# RiskChemi_Sensors_V2_05M1.net
KiCad netlist of a schematic drawn in Altium Designer
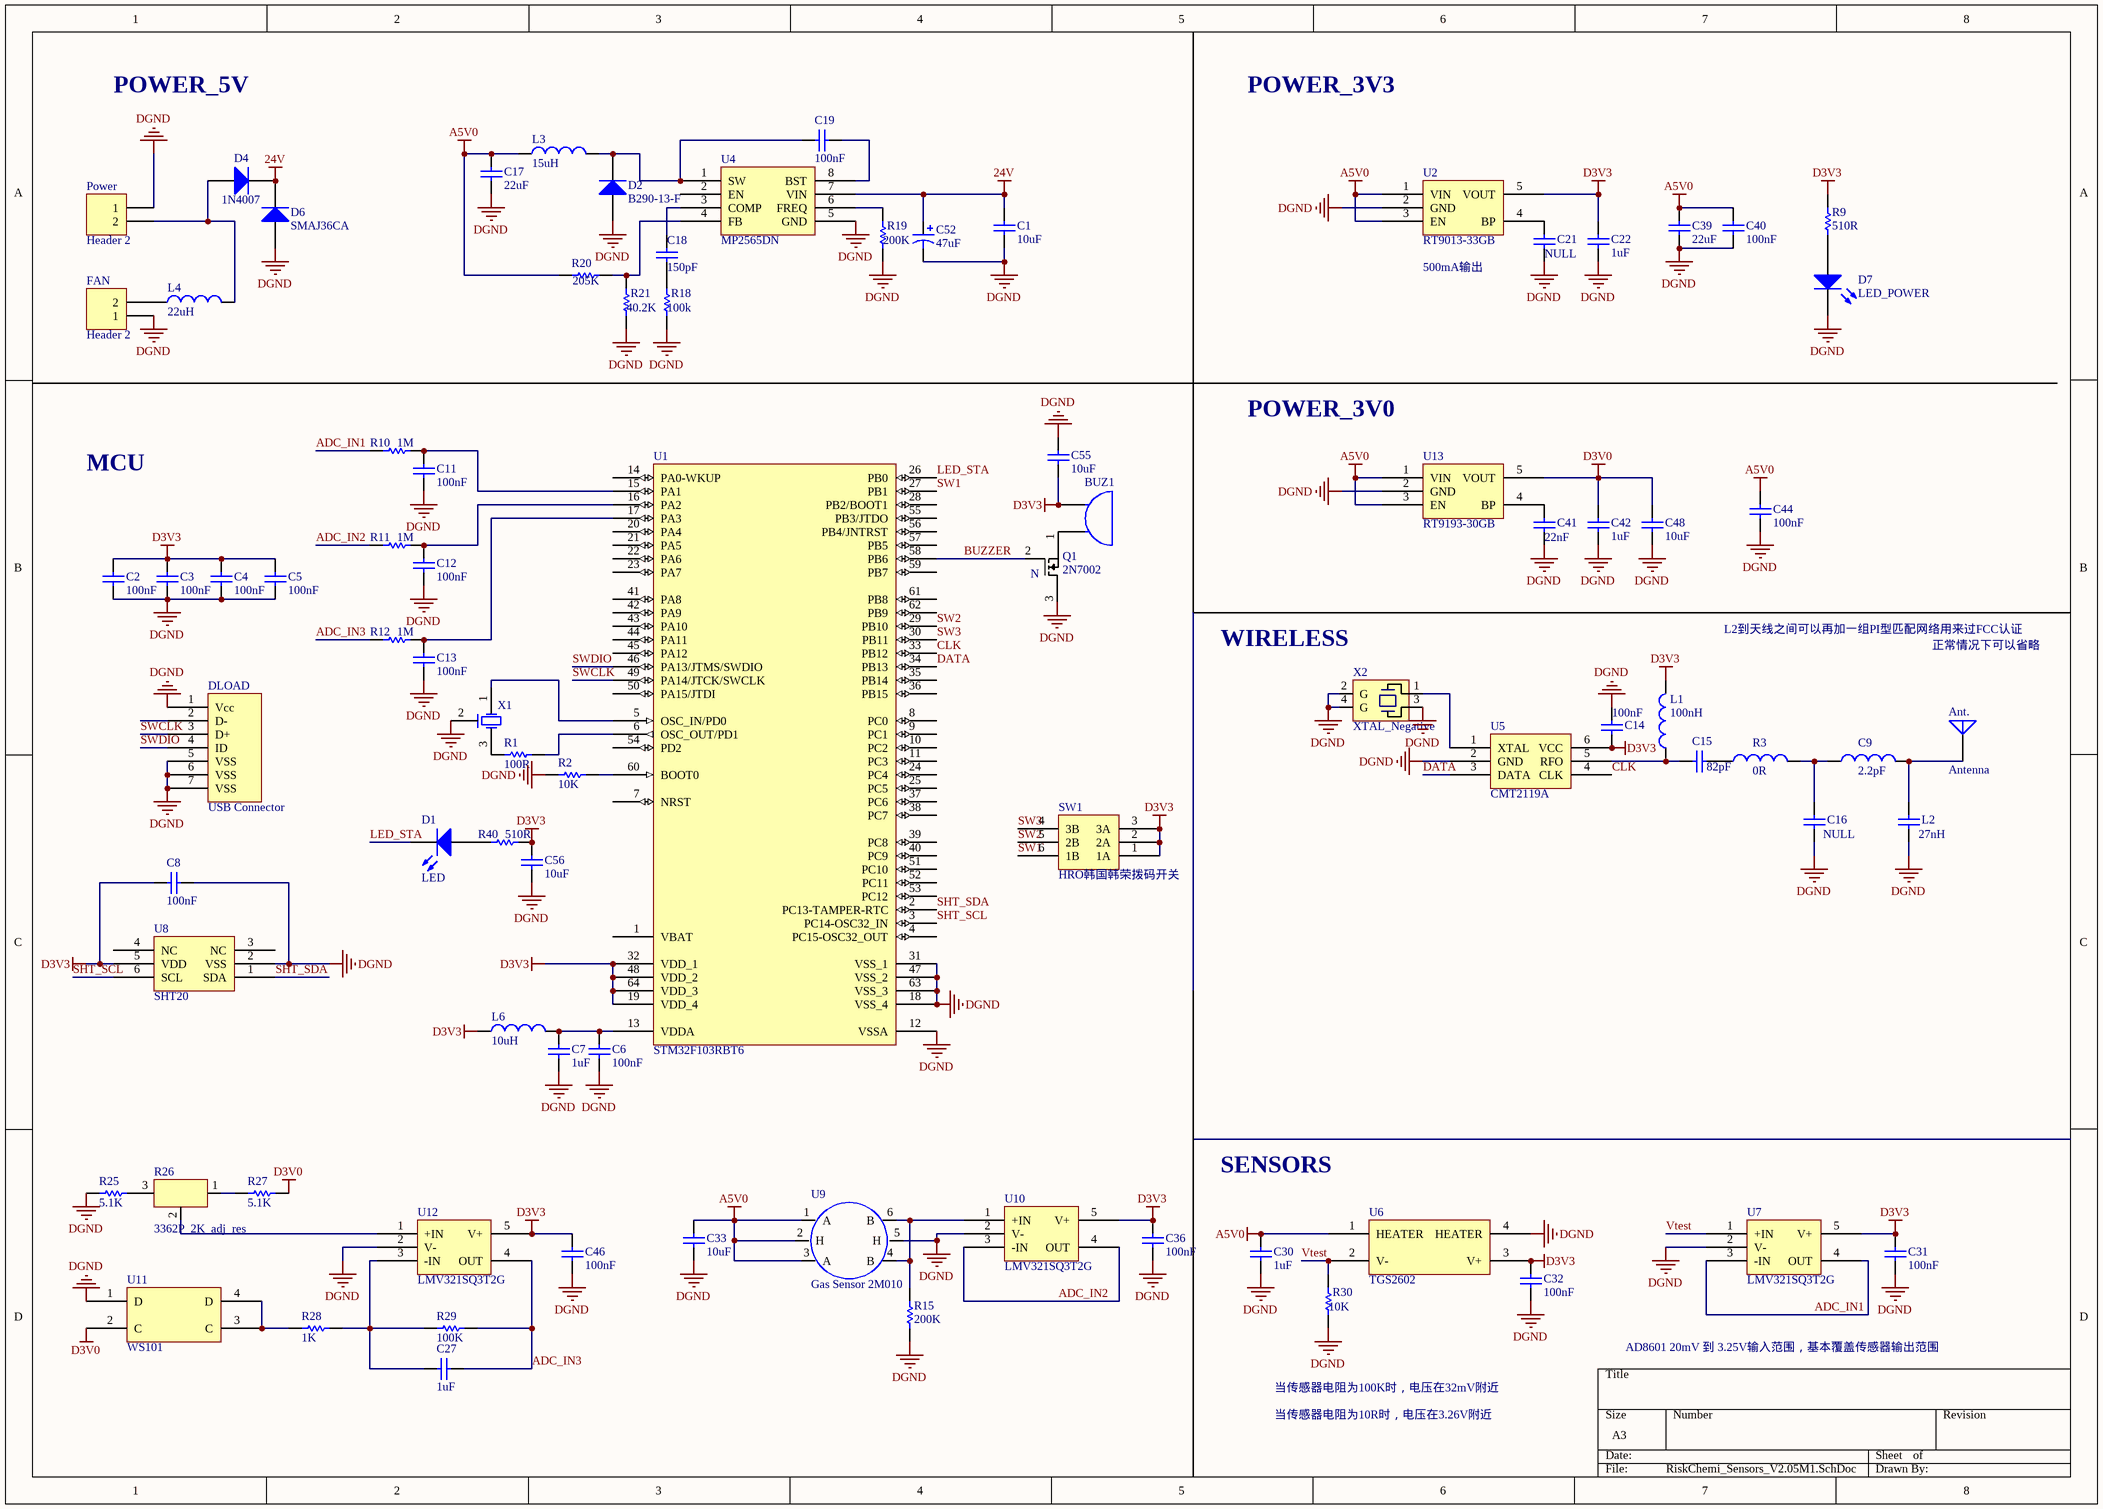
[diagram p0: RiskChemi_Sensors_V2.05M1.SchDoc]

(export (version "E")
  (design (tool "Eeschema 10.0.6"))
  (components
    (comp (ref "Ant.")
      (value "Antenna")
      (footprint "PIN1")
      (description "Generic Antenna")
      (fields (field (name "PUBLISHER") "Altium Limited"))
      (libsource (lib "Miscellaneous Devices") (part "Antenna"))
    )
    (comp (ref "BUZ1")
      (value "BUZZER 0905 through hole")
      (footprint "BUZ0905")
      (description "Buzzer")
      (libsource (lib "杂元件库") (part "BUZZER"))
    )
    (comp (ref "C1")
      (value "10uF")
      (footprint "0805")
      (description "Capacitor,50V")
      (fields (field (name "PUBLISHER") "Altium Limited"))
      (libsource (lib "Miscellaneous Devices") (part "Cap"))
    )
    (comp (ref "C2")
      (value "100nF")
      (footprint "BinFeng:0603")
      (description "Capacitor")
      (fields (field (name "PUBLISHER") "Altium Limited"))
      (libsource (lib "Miscellaneous Devices") (part "Cap"))
    )
    (comp (ref "C3")
      (value "100nF")
      (footprint "BinFeng:0603")
      (description "Capacitor")
      (fields (field (name "PUBLISHER") "Altium Limited"))
      (libsource (lib "Miscellaneous Devices") (part "Cap"))
    )
    (comp (ref "C4")
      (value "100nF")
      (footprint "BinFeng:0603")
      (description "Capacitor")
      (fields (field (name "PUBLISHER") "Altium Limited"))
      (libsource (lib "Miscellaneous Devices") (part "Cap"))
    )
    (comp (ref "C5")
      (value "100nF")
      (footprint "BinFeng:0603")
      (description "Capacitor")
      (fields (field (name "PUBLISHER") "Altium Limited"))
      (libsource (lib "Miscellaneous Devices") (part "Cap"))
    )
    (comp (ref "C6")
      (value "100nF")
      (footprint "BinFeng:0603")
      (description "Capacitor")
      (fields (field (name "PUBLISHER") "Altium Limited"))
      (libsource (lib "Miscellaneous Devices") (part "Cap"))
    )
    (comp (ref "C7")
      (value "1uF")
      (footprint "BinFeng:0603")
      (description "Capacitor")
      (fields (field (name "PUBLISHER") "Altium Limited"))
      (libsource (lib "Miscellaneous Devices") (part "Cap"))
    )
    (comp (ref "C8")
      (value "100nF")
      (footprint "BinFeng:0603")
      (description "Capacitor")
      (fields (field (name "PUBLISHER") "Altium Limited"))
      (libsource (lib "Miscellaneous Devices") (part "Cap"))
    )
    (comp (ref "C9")
      (value "2.2pF")
      (footprint "0603C")
      (description "Inductor")
      (fields (field (name "PUBLISHER") "Altium Limited"))
      (libsource (lib "Miscellaneous Devices") (part "Inductor"))
    )
    (comp (ref "C11")
      (value "100nF")
      (footprint "BinFeng:0603")
      (description "Capacitor")
      (fields (field (name "PUBLISHER") "Altium Limited"))
      (libsource (lib "Miscellaneous Devices") (part "Cap"))
    )
    (comp (ref "C12")
      (value "100nF")
      (footprint "BinFeng:0603")
      (description "Capacitor")
      (fields (field (name "PUBLISHER") "Altium Limited"))
      (libsource (lib "Miscellaneous Devices") (part "Cap"))
    )
    (comp (ref "C13")
      (value "100nF")
      (footprint "BinFeng:0603")
      (description "Capacitor")
      (fields (field (name "PUBLISHER") "Altium Limited"))
      (libsource (lib "Miscellaneous Devices") (part "Cap"))
    )
    (comp (ref "C14")
      (value "100nF")
      (footprint "BinFeng:0402")
      (description "Capacitor")
      (fields (field (name "PUBLISHER") "Altium Limited"))
      (libsource (lib "Miscellaneous Devices") (part "Cap"))
    )
    (comp (ref "C15")
      (value "82pF")
      (footprint "BinFeng:0402")
      (description "Capacitor")
      (fields (field (name "PUBLISHER") "Altium Limited"))
      (libsource (lib "Miscellaneous Devices") (part "Cap"))
    )
    (comp (ref "C16")
      (value "NULL")
      (footprint "BinFeng:0402")
      (description "Capacitor")
      (fields (field (name "PUBLISHER") "Altium Limited"))
      (libsource (lib "Miscellaneous Devices") (part "Cap"))
    )
    (comp (ref "C17")
      (value "22uF")
      (footprint "0805")
      (description "Capacitor,50V")
      (fields (field (name "PUBLISHER") "Altium Limited"))
      (libsource (lib "Miscellaneous Devices") (part "Cap"))
    )
    (comp (ref "C18")
      (value "150pF")
      (footprint "BinFeng:0603")
      (description "Capacitor")
      (fields (field (name "PUBLISHER") "Altium Limited"))
      (libsource (lib "Miscellaneous Devices") (part "Cap"))
    )
    (comp (ref "C19")
      (value "100nF")
      (footprint "BinFeng:0603")
      (description "Capacitor")
      (fields (field (name "PUBLISHER") "Altium Limited"))
      (libsource (lib "Miscellaneous Devices") (part "Cap"))
    )
    (comp (ref "C21")
      (value "NULL")
      (footprint "BinFeng:0402")
      (description "Capacitor")
      (fields (field (name "PUBLISHER") "Altium Limited"))
      (libsource (lib "Miscellaneous Devices") (part "Cap"))
    )
    (comp (ref "C22")
      (value "1uF")
      (footprint "BinFeng:0402")
      (description "Capacitor")
      (fields (field (name "PUBLISHER") "Altium Limited"))
      (libsource (lib "Miscellaneous Devices") (part "Cap"))
    )
    (comp (ref "C27")
      (value "1uF")
      (footprint "BinFeng:0603")
      (description "Capacitor")
      (fields (field (name "PUBLISHER") "Altium Limited"))
      (libsource (lib "Miscellaneous Devices") (part "Cap"))
    )
    (comp (ref "C30")
      (value "1uF")
      (footprint "BinFeng:0603")
      (description "Capacitor")
      (fields (field (name "PUBLISHER") "Altium Limited"))
      (libsource (lib "Miscellaneous Devices") (part "Cap"))
    )
    (comp (ref "C31")
      (value "100nF")
      (footprint "BinFeng:0603")
      (description "Capacitor")
      (fields (field (name "PUBLISHER") "Altium Limited"))
      (libsource (lib "Miscellaneous Devices") (part "Cap"))
    )
    (comp (ref "C32")
      (value "100nF")
      (footprint "BinFeng:0603")
      (description "Capacitor")
      (fields (field (name "PUBLISHER") "Altium Limited"))
      (libsource (lib "Miscellaneous Devices") (part "Cap"))
    )
    (comp (ref "C33")
      (value "10uF")
      (footprint "0805")
      (description "Capacitor")
      (fields (field (name "PUBLISHER") "Altium Limited"))
      (libsource (lib "Miscellaneous Devices") (part "Cap"))
    )
    (comp (ref "C36")
      (value "100nF")
      (footprint "BinFeng:0603")
      (description "Capacitor")
      (fields (field (name "PUBLISHER") "Altium Limited"))
      (libsource (lib "Miscellaneous Devices") (part "Cap"))
    )
    (comp (ref "C39")
      (value "22uF")
      (footprint "1206")
      (description "Capacitor")
      (fields (field (name "PUBLISHER") "Altium Limited"))
      (libsource (lib "Miscellaneous Devices") (part "Cap"))
    )
    (comp (ref "C40")
      (value "100nF")
      (footprint "BinFeng:0402")
      (description "Capacitor")
      (fields (field (name "PUBLISHER") "Altium Limited"))
      (libsource (lib "Miscellaneous Devices") (part "Cap"))
    )
    (comp (ref "C41")
      (value "22nF")
      (footprint "BinFeng:0402")
      (description "Capacitor")
      (fields (field (name "PUBLISHER") "Altium Limited"))
      (libsource (lib "Miscellaneous Devices") (part "Cap"))
    )
    (comp (ref "C42")
      (value "1uF")
      (footprint "BinFeng:0402")
      (description "Capacitor")
      (fields (field (name "PUBLISHER") "Altium Limited"))
      (libsource (lib "Miscellaneous Devices") (part "Cap"))
    )
    (comp (ref "C44")
      (value "100nF")
      (footprint "BinFeng:0402")
      (description "Capacitor")
      (fields (field (name "PUBLISHER") "Altium Limited"))
      (libsource (lib "Miscellaneous Devices") (part "Cap"))
    )
    (comp (ref "C46")
      (value "100nF")
      (footprint "BinFeng:0603")
      (description "Capacitor")
      (fields (field (name "PUBLISHER") "Altium Limited"))
      (libsource (lib "Miscellaneous Devices") (part "Cap"))
    )
    (comp (ref "C48")
      (value "10uF")
      (footprint "0805")
      (description "Capacitor")
      (fields (field (name "PUBLISHER") "Altium Limited"))
      (libsource (lib "Miscellaneous Devices") (part "Cap"))
    )
    (comp (ref "C52")
      (value "47uF")
      (footprint "cap_pol_8*10.2")
      (description "Polarized Capacitor (Radial)")
      (fields (field (name "PUBLISHER") "Altium Limited"))
      (libsource (lib "Miscellaneous Devices") (part "Cap Pol1"))
    )
    (comp (ref "C55")
      (value "10uF")
      (footprint "0805")
      (description "Capacitor")
      (fields (field (name "PUBLISHER") "Altium Limited"))
      (libsource (lib "Miscellaneous Devices") (part "Cap"))
    )
    (comp (ref "C56")
      (value "10uF")
      (footprint "0805")
      (description "Capacitor")
      (fields (field (name "PUBLISHER") "Altium Limited"))
      (libsource (lib "Miscellaneous Devices") (part "Cap"))
    )
    (comp (ref "D1")
      (value "LED")
      (footprint "1206_LED")
      (description "Typical INFRARED GaAs LED")
      (fields (field (name "PUBLISHER") "Altium Limited"))
      (libsource (lib "Miscellaneous Devices") (part "LED0"))
    )
    (comp (ref "D2")
      (value "B290-13-F")
      (footprint "B290")
      (description "Default Diode")
      (fields (field (name "PUBLISHER") "Altium Limited"))
      (libsource (lib "Miscellaneous Devices") (part "Diode"))
    )
    (comp (ref "D4")
      (value "1N4007")
      (footprint "6032_pol")
      (description "1 Amp General Purpose Rectifier")
      (fields (field (name "PUBLISHER") "Altium Limited"))
      (libsource (lib "Miscellaneous Devices") (part "Diode 1N4007"))
    )
    (comp (ref "D6")
      (value "SMAJ36CA")
      (footprint "B290")
      (description "1 Amp General Purpose Rectifier")
      (fields (field (name "PUBLISHER") "Altium Limited"))
      (libsource (lib "Miscellaneous Devices") (part "Diode 1N4007"))
    )
    (comp (ref "D7")
      (value "LED_POWER")
      (footprint "1206_LED")
      (description "Typical INFRARED GaAs LED")
      (fields (field (name "PUBLISHER") "Altium Limited"))
      (libsource (lib "Miscellaneous Devices") (part "LED0"))
    )
    (comp (ref "DLOAD")
      (value "USB Connector")
      (footprint "Mini_USB")
      (libsource (lib "BinFeng_Connectors") (part "Component_1"))
    )
    (comp (ref "FAN")
      (value "Header 2")
      (footprint "HDR1X2")
      (description "Header, 2-Pin")
      (fields (field (name "PUBLISHER") "Altium Limited"))
      (libsource (lib "Miscellaneous Connectors") (part "Header 2"))
    )
    (comp (ref "L1")
      (value "100nH")
      (footprint "0603C")
      (description "Inductor")
      (fields (field (name "PUBLISHER") "Altium Limited"))
      (libsource (lib "Miscellaneous Devices") (part "Inductor"))
    )
    (comp (ref "L2")
      (value "27nH")
      (footprint "BinFeng:0402")
      (description "Capacitor")
      (fields (field (name "PUBLISHER") "Altium Limited"))
      (libsource (lib "Miscellaneous Devices") (part "Cap"))
    )
    (comp (ref "L3")
      (value "15uH")
      (footprint "4*4 Inductor")
      (description "Inductor, 1A")
      (fields (field (name "PUBLISHER") "Altium Limited"))
      (libsource (lib "Miscellaneous Devices") (part "Inductor"))
    )
    (comp (ref "L4")
      (value "22uH")
      (footprint "10*10Inductor")
      (description "Inductor, 1A")
      (fields (field (name "PUBLISHER") "Altium Limited"))
      (libsource (lib "Miscellaneous Devices") (part "Inductor"))
    )
    (comp (ref "L6")
      (value "10uH")
      (footprint "0805")
      (description "Inductor")
      (fields (field (name "PUBLISHER") "Altium Limited"))
      (libsource (lib "Miscellaneous Devices") (part "Inductor"))
    )
    (comp (ref "Power")
      (value "Header 2")
      (footprint "HDR1X2")
      (description "Header, 2-Pin")
      (fields (field (name "PUBLISHER") "Altium Limited"))
      (libsource (lib "") (part "Header 2_1"))
    )
    (comp (ref "Q1") (value "2N7002") (footprint "2N7002") (libsource (lib "seeder") (part "N-MOSFET")))
    (comp (ref "R1")
      (value "100R")
      (footprint "BinFeng:0603")
      (description "Resistor")
      (fields (field (name "PUBLISHER") "Altium Limited"))
      (libsource (lib "Miscellaneous Devices") (part "Res1"))
    )
    (comp (ref "R2")
      (value "10K")
      (footprint "BinFeng:0603")
      (description "Resistor")
      (fields (field (name "PUBLISHER") "Altium Limited"))
      (libsource (lib "Miscellaneous Devices") (part "Res1"))
    )
    (comp (ref "R3")
      (value "0R")
      (footprint "0603C")
      (description "Inductor")
      (fields (field (name "PUBLISHER") "Altium Limited"))
      (libsource (lib "Miscellaneous Devices") (part "Inductor"))
    )
    (comp (ref "R9")
      (value "510R")
      (footprint "BinFeng:0603")
      (description "Resistor")
      (fields (field (name "PUBLISHER") "Altium Limited"))
      (libsource (lib "Miscellaneous Devices") (part "Res1"))
    )
    (comp (ref "R10")
      (value "1M")
      (footprint "BinFeng:0603")
      (description "Resistor")
      (fields (field (name "PUBLISHER") "Altium Limited"))
      (libsource (lib "Miscellaneous Devices") (part "Res1"))
    )
    (comp (ref "R11")
      (value "1M")
      (footprint "BinFeng:0603")
      (description "Resistor")
      (fields (field (name "PUBLISHER") "Altium Limited"))
      (libsource (lib "Miscellaneous Devices") (part "Res1"))
    )
    (comp (ref "R12")
      (value "1M")
      (footprint "BinFeng:0603")
      (description "Resistor")
      (fields (field (name "PUBLISHER") "Altium Limited"))
      (libsource (lib "Miscellaneous Devices") (part "Res1"))
    )
    (comp (ref "R15")
      (value "200K")
      (footprint "BinFeng:0603C")
      (description "Resistor")
      (fields (field (name "Comment") "Res1") (field (name "PUBLISHER") "Altium Limited"))
      (libsource (lib "Miscellaneous Devices") (part "Res1"))
    )
    (comp (ref "R18")
      (value "100k")
      (footprint "BinFeng:0603")
      (description "Resistor")
      (fields (field (name "PUBLISHER") "Altium Limited"))
      (libsource (lib "Miscellaneous Devices") (part "Res1"))
    )
    (comp (ref "R19")
      (value "200K")
      (footprint "BinFeng:0402")
      (description "Resistor")
      (fields (field (name "PUBLISHER") "Altium Limited"))
      (libsource (lib "Miscellaneous Devices") (part "Res1"))
    )
    (comp (ref "R20")
      (value "205K")
      (footprint "BinFeng:0603")
      (description "Resistor")
      (fields (field (name "PUBLISHER") "Altium Limited"))
      (libsource (lib "Miscellaneous Devices") (part "Res1"))
    )
    (comp (ref "R21")
      (value "40.2K")
      (footprint "BinFeng:0603")
      (description "Resistor")
      (fields (field (name "PUBLISHER") "Altium Limited"))
      (libsource (lib "Miscellaneous Devices") (part "Res1"))
    )
    (comp (ref "R25")
      (value "5.1K")
      (footprint "BinFeng:0603")
      (description "Resistor")
      (fields (field (name "PUBLISHER") "Altium Limited"))
      (libsource (lib "Miscellaneous Devices") (part "Res1"))
    )
    (comp (ref "R26")
      (value "3362P_2K_adj_res")
      (footprint "res_adj")
      (libsource (lib "BinFeng_IC") (part "res_adj"))
    )
    (comp (ref "R27")
      (value "5.1K")
      (footprint "BinFeng:0603")
      (description "Resistor")
      (fields (field (name "PUBLISHER") "Altium Limited"))
      (libsource (lib "Miscellaneous Devices") (part "Res1"))
    )
    (comp (ref "R28")
      (value "1K")
      (footprint "BinFeng:0603")
      (description "Resistor")
      (fields (field (name "PUBLISHER") "Altium Limited"))
      (libsource (lib "Miscellaneous Devices") (part "Res1"))
    )
    (comp (ref "R29")
      (value "100K")
      (footprint "BinFeng:0603")
      (description "Resistor")
      (fields (field (name "PUBLISHER") "Altium Limited"))
      (libsource (lib "Miscellaneous Devices") (part "Res1"))
    )
    (comp (ref "R30")
      (value "10K")
      (footprint "BinFeng:0603")
      (description "Resistor")
      (fields (field (name "PUBLISHER") "Altium Limited"))
      (libsource (lib "Miscellaneous Devices") (part "Res1"))
    )
    (comp (ref "R40")
      (value "510R")
      (footprint "BinFeng:0603")
      (description "Resistor")
      (fields (field (name "PUBLISHER") "Altium Limited"))
      (libsource (lib "Miscellaneous Devices") (part "Res1"))
    )
    (comp (ref "SW1")
      (value "HRO韩国韩荣拨码开关")
      (footprint "SW_6P_HRO")
      (libsource (lib "BinFeng_IC") (part "SW_6P"))
    )
    (comp (ref "U1")
      (value "STM32F103RBT6")
      (footprint "LQFP64_N")
      (description "STM32 ARM-based 32-bit MCU with 64 Kbytes Flash, 64-pin LQFP, Industrial Temperature")
      (fields (field (name "PUBLISHER") "Altium Limited"))
      (libsource (lib "ST Microcontroller 32-Bit STM32") (part "STM32F103R8T6"))
    )
    (comp (ref "U2")
      (value "RT9013-33GB")
      (footprint "SOT-23-5")
      (libsource (lib "BinFeng_IC") (part "RT9193"))
    )
    (comp (ref "U4")
      (value "MP2565DN")
      (footprint "so-8")
      (description "DCDC 4.5V~28V input 1.8V ~5V output low power")
      (libsource (lib "BinFeng_IC") (part "MP1584"))
    )
    (comp (ref "U5")
      (value "CMT2119A")
      (footprint "sot23-6")
      (libsource (lib "BinFeng_IC") (part "CMT2119A"))
    )
    (comp (ref "U6")
      (value "TGS2602")
      (footprint "Gas Sensor TGS2602 Slot")
      (description "VOC sensor")
      (libsource (lib "BinFeng_IC") (part "TGS2602"))
    )
    (comp (ref "U7")
      (value "LMV321SQ3T2G")
      (footprint "SC-70-5")
      (libsource (lib "BinFeng_IC") (part "LMV321SQ3T2G"))
    )
    (comp (ref "U8") (value "SHT20") (footprint "SHT20") (libsource (lib "BinFeng_IC") (part "SHT20")))
    (comp (ref "U9")
      (value "Gas Sensor 2M010")
      (footprint "Gas Sensor 2M010 Slot")
      (libsource (lib "BinFeng_IC") (part "Gas Sensor"))
    )
    (comp (ref "U10")
      (value "LMV321SQ3T2G")
      (footprint "SC-70-5")
      (libsource (lib "BinFeng_IC") (part "LMV321SQ3T2G"))
    )
    (comp (ref "U11")
      (value "WS101")
      (footprint "Gas_Sensor_WS101_Slot")
      (libsource (lib "BinFeng_IC") (part "Gas Sensor_WS101"))
    )
    (comp (ref "U12")
      (value "LMV321SQ3T2G")
      (footprint "SC-70-5")
      (libsource (lib "BinFeng_IC") (part "LMV321SQ3T2G"))
    )
    (comp (ref "U13")
      (value "RT9193-30GB")
      (footprint "SOT-23-5")
      (libsource (lib "BinFeng_IC") (part "RT9193"))
    )
    (comp (ref "X1") (value "8M smd") (footprint "8Mhz_XTAL") (libsource (lib "Schlib1") (part "8M smd")))
    (comp (ref "X2")
      (value "XTAL_Negative")
      (footprint "XTAL3225")
      (libsource (lib "BinFeng_IC") (part "XTAL_Negative"))
    )
  )
  (nets
    (net (code "1") (name "/ADC_IN1") (class "Default")
      (node (ref "R10") (pin "1") (pinfunction "1_1") (pintype "passive"))
      (node (ref "U7") (pin "3") (pinfunction "-IN_3") (pintype "passive"))
      (node (ref "U7") (pin "4") (pinfunction "OUT_4") (pintype "passive"))
    )
    (net (code "2") (name "/ADC_IN2") (class "Default")
      (node (ref "R11") (pin "1") (pinfunction "1_1") (pintype "passive"))
      (node (ref "U10") (pin "3") (pinfunction "-IN_3") (pintype "passive"))
      (node (ref "U10") (pin "4") (pinfunction "OUT_4") (pintype "passive"))
    )
    (net (code "3") (name "/ADC_IN3") (class "Default")
      (node (ref "C27") (pin "1") (pinfunction "1_1") (pintype "passive"))
      (node (ref "R12") (pin "1") (pinfunction "1_1") (pintype "passive"))
      (node (ref "R29") (pin "2") (pinfunction "2_2") (pintype "passive"))
      (node (ref "U12") (pin "4") (pinfunction "OUT_4") (pintype "passive"))
    )
    (net (code "4") (name "/BUZZER") (class "Default")
      (node (ref "Q1") (pin "2") (pinfunction "G_2") (pintype "passive"))
      (node (ref "U1") (pin "58") (pinfunction "PB6_58") (pintype "bidirectional"))
    )
    (net (code "5") (name "/CLK") (class "Default")
      (node (ref "U1") (pin "33") (pinfunction "PB12_33") (pintype "bidirectional"))
      (node (ref "U5") (pin "4") (pinfunction "CLK_4") (pintype "passive"))
    )
    (net (code "6") (name "/DATA") (class "Default")
      (node (ref "U1") (pin "34") (pinfunction "PB13_34") (pintype "bidirectional"))
      (node (ref "U5") (pin "3") (pinfunction "DATA_3") (pintype "passive"))
    )
    (net (code "7") (name "/LED_STA") (class "Default")
      (node (ref "D1") (pin "2") (pinfunction "K_2") (pintype "passive"))
      (node (ref "U1") (pin "26") (pinfunction "PB0_26") (pintype "bidirectional"))
    )
    (net (code "8") (name "/SHT_SCL") (class "Default")
      (node (ref "U1") (pin "3") (pinfunction "PC14-OSC32_IN_3") (pintype "bidirectional"))
      (node (ref "U8") (pin "6") (pinfunction "SCL_6") (pintype "passive"))
    )
    (net (code "9") (name "/SHT_SDA") (class "Default")
      (node (ref "U1") (pin "2") (pinfunction "PC13-TAMPER-RTC_2") (pintype "bidirectional"))
      (node (ref "U8") (pin "1") (pinfunction "SDA_1") (pintype "passive"))
    )
    (net (code "10") (name "/SW1") (class "Default")
      (node (ref "SW1") (pin "6") (pinfunction "1B_6") (pintype "passive"))
      (node (ref "U1") (pin "27") (pinfunction "PB1_27") (pintype "bidirectional"))
    )
    (net (code "11") (name "/SW2") (class "Default")
      (node (ref "SW1") (pin "5") (pinfunction "2B_5") (pintype "passive"))
      (node (ref "U1") (pin "29") (pinfunction "PB10_29") (pintype "bidirectional"))
    )
    (net (code "12") (name "/SW3") (class "Default")
      (node (ref "SW1") (pin "4") (pinfunction "3B_4") (pintype "passive"))
      (node (ref "U1") (pin "30") (pinfunction "PB11_30") (pintype "bidirectional"))
    )
    (net (code "13") (name "/SWCLK") (class "Default")
      (node (ref "DLOAD") (pin "3") (pinfunction "D+_3") (pintype "passive"))
      (node (ref "U1") (pin "49") (pinfunction "PA14/JTCK/SWCLK_49") (pintype "bidirectional"))
    )
    (net (code "14") (name "/SWDIO") (class "Default")
      (node (ref "DLOAD") (pin "4") (pinfunction "ID_4") (pintype "passive"))
      (node (ref "U1") (pin "46") (pinfunction "PA13/JTMS/SWDIO_46") (pintype "bidirectional"))
    )
    (net (code "15") (name "/Vtest") (class "Default")
      (node (ref "R30") (pin "2") (pinfunction "2_2") (pintype "passive"))
      (node (ref "U6") (pin "2") (pinfunction "V-_2") (pintype "passive"))
      (node (ref "U7") (pin "1") (pinfunction "+IN_1") (pintype "passive"))
    )
    (net (code "16") (name "24V") (class "Default")
      (node (ref "C1") (pin "2") (pinfunction "2_2") (pintype "passive"))
      (node (ref "C52") (pin "1") (pinfunction "1_1") (pintype "passive"))
      (node (ref "D4") (pin "2") (pinfunction "K_2") (pintype "passive"))
      (node (ref "D6") (pin "2") (pinfunction "K_2") (pintype "passive"))
      (node (ref "U4") (pin "7") (pinfunction "VIN_7") (pintype "passive"))
    )
    (net (code "17") (name "A5V0") (class "Default")
      (node (ref "C17") (pin "2") (pinfunction "2_2") (pintype "passive"))
      (node (ref "C30") (pin "2") (pinfunction "2_2") (pintype "passive"))
      (node (ref "C33") (pin "2") (pinfunction "2_2") (pintype "passive"))
      (node (ref "C39") (pin "1") (pinfunction "1_1") (pintype "passive"))
      (node (ref "C40") (pin "2") (pinfunction "2_2") (pintype "passive"))
      (node (ref "C44") (pin "2") (pinfunction "2_2") (pintype "passive"))
      (node (ref "L3") (pin "1") (pinfunction "1_1") (pintype "passive"))
      (node (ref "R20") (pin "2") (pinfunction "2_2") (pintype "passive"))
      (node (ref "U13") (pin "1") (pinfunction "VIN_1") (pintype "passive"))
      (node (ref "U13") (pin "3") (pinfunction "EN_3") (pintype "passive"))
      (node (ref "U2") (pin "1") (pinfunction "VIN_1") (pintype "passive"))
      (node (ref "U2") (pin "3") (pinfunction "EN_3") (pintype "passive"))
      (node (ref "U6") (pin "1") (pinfunction "HEATER_1") (pintype "passive"))
      (node (ref "U9") (pin "1") (pinfunction "A_1") (pintype "passive"))
      (node (ref "U9") (pin "2") (pinfunction "H_2") (pintype "passive"))
      (node (ref "U9") (pin "3") (pinfunction "A_3") (pintype "passive"))
    )
    (net (code "18") (name "D3V0") (class "Default")
      (node (ref "C42") (pin "2") (pinfunction "2_2") (pintype "passive"))
      (node (ref "C48") (pin "2") (pinfunction "2_2") (pintype "passive"))
      (node (ref "R27") (pin "2") (pinfunction "2_2") (pintype "passive"))
      (node (ref "U11") (pin "2") (pinfunction "C_2") (pintype "passive"))
      (node (ref "U13") (pin "5") (pinfunction "VOUT_5") (pintype "passive"))
    )
    (net (code "19") (name "D3V3") (class "Default")
      (node (ref "BUZ1") (pin "1") (pinfunction "A_1") (pintype "passive"))
      (node (ref "C14") (pin "2") (pinfunction "2_2") (pintype "passive"))
      (node (ref "C2") (pin "2") (pinfunction "2_2") (pintype "passive"))
      (node (ref "C22") (pin "2") (pinfunction "2_2") (pintype "passive"))
      (node (ref "C3") (pin "2") (pinfunction "2_2") (pintype "passive"))
      (node (ref "C31") (pin "2") (pinfunction "2_2") (pintype "passive"))
      (node (ref "C32") (pin "2") (pinfunction "2_2") (pintype "passive"))
      (node (ref "C36") (pin "2") (pinfunction "2_2") (pintype "passive"))
      (node (ref "C4") (pin "2") (pinfunction "2_2") (pintype "passive"))
      (node (ref "C46") (pin "2") (pinfunction "2_2") (pintype "passive"))
      (node (ref "C5") (pin "2") (pinfunction "2_2") (pintype "passive"))
      (node (ref "C55") (pin "2") (pinfunction "2_2") (pintype "passive"))
      (node (ref "C56") (pin "2") (pinfunction "2_2") (pintype "passive"))
      (node (ref "C8") (pin "2") (pinfunction "2_2") (pintype "passive"))
      (node (ref "L1") (pin "2") (pinfunction "2_2") (pintype "passive"))
      (node (ref "L6") (pin "1") (pinfunction "1_1") (pintype "passive"))
      (node (ref "R40") (pin "2") (pinfunction "2_2") (pintype "passive"))
      (node (ref "R9") (pin "2") (pinfunction "2_2") (pintype "passive"))
      (node (ref "SW1") (pin "1") (pinfunction "1A_1") (pintype "passive"))
      (node (ref "SW1") (pin "2") (pinfunction "2A_2") (pintype "passive"))
      (node (ref "SW1") (pin "3") (pinfunction "3A_3") (pintype "passive"))
      (node (ref "U1") (pin "19") (pinfunction "VDD_4_19") (pintype "power_in"))
      (node (ref "U1") (pin "32") (pinfunction "VDD_1_32") (pintype "power_in"))
      (node (ref "U1") (pin "48") (pinfunction "VDD_2_48") (pintype "power_in"))
      (node (ref "U1") (pin "64") (pinfunction "VDD_3_64") (pintype "power_in"))
      (node (ref "U10") (pin "5") (pinfunction "V+_5") (pintype "passive"))
      (node (ref "U12") (pin "5") (pinfunction "V+_5") (pintype "passive"))
      (node (ref "U2") (pin "5") (pinfunction "VOUT_5") (pintype "passive"))
      (node (ref "U5") (pin "6") (pinfunction "VCC_6") (pintype "passive"))
      (node (ref "U6") (pin "3") (pinfunction "V+_3") (pintype "passive"))
      (node (ref "U7") (pin "5") (pinfunction "V+_5") (pintype "passive"))
      (node (ref "U8") (pin "5") (pinfunction "VDD_5") (pintype "passive"))
    )
    (net (code "20") (name "DGND") (class "Default")
      (node (ref "C1") (pin "1") (pinfunction "1_1") (pintype "passive"))
      (node (ref "C11") (pin "2") (pinfunction "2_2") (pintype "passive"))
      (node (ref "C12") (pin "1") (pinfunction "1_1") (pintype "passive"))
      (node (ref "C13") (pin "1") (pinfunction "1_1") (pintype "passive"))
      (node (ref "C14") (pin "1") (pinfunction "1_1") (pintype "passive"))
      (node (ref "C16") (pin "1") (pinfunction "1_1") (pintype "passive"))
      (node (ref "C17") (pin "1") (pinfunction "1_1") (pintype "passive"))
      (node (ref "C2") (pin "1") (pinfunction "1_1") (pintype "passive"))
      (node (ref "C21") (pin "1") (pinfunction "1_1") (pintype "passive"))
      (node (ref "C22") (pin "1") (pinfunction "1_1") (pintype "passive"))
      (node (ref "C3") (pin "1") (pinfunction "1_1") (pintype "passive"))
      (node (ref "C30") (pin "1") (pinfunction "1_1") (pintype "passive"))
      (node (ref "C31") (pin "1") (pinfunction "1_1") (pintype "passive"))
      (node (ref "C32") (pin "1") (pinfunction "1_1") (pintype "passive"))
      (node (ref "C33") (pin "1") (pinfunction "1_1") (pintype "passive"))
      (node (ref "C36") (pin "1") (pinfunction "1_1") (pintype "passive"))
      (node (ref "C39") (pin "2") (pinfunction "2_2") (pintype "passive"))
      (node (ref "C4") (pin "1") (pinfunction "1_1") (pintype "passive"))
      (node (ref "C40") (pin "1") (pinfunction "1_1") (pintype "passive"))
      (node (ref "C41") (pin "1") (pinfunction "1_1") (pintype "passive"))
      (node (ref "C42") (pin "1") (pinfunction "1_1") (pintype "passive"))
      (node (ref "C44") (pin "1") (pinfunction "1_1") (pintype "passive"))
      (node (ref "C46") (pin "1") (pinfunction "1_1") (pintype "passive"))
      (node (ref "C48") (pin "1") (pinfunction "1_1") (pintype "passive"))
      (node (ref "C5") (pin "1") (pinfunction "1_1") (pintype "passive"))
      (node (ref "C52") (pin "2") (pinfunction "2_2") (pintype "passive"))
      (node (ref "C55") (pin "1") (pinfunction "1_1") (pintype "passive"))
      (node (ref "C56") (pin "1") (pinfunction "1_1") (pintype "passive"))
      (node (ref "C6") (pin "1") (pinfunction "1_1") (pintype "passive"))
      (node (ref "C7") (pin "1") (pinfunction "1_1") (pintype "passive"))
      (node (ref "C8") (pin "1") (pinfunction "1_1") (pintype "passive"))
      (node (ref "D2") (pin "1") (pinfunction "A_1") (pintype "passive"))
      (node (ref "D6") (pin "1") (pinfunction "A_1") (pintype "passive"))
      (node (ref "D7") (pin "2") (pinfunction "K_2") (pintype "passive"))
      (node (ref "DLOAD") (pin "1") (pinfunction "Vcc_1") (pintype "passive"))
      (node (ref "DLOAD") (pin "5") (pinfunction "VSS_5") (pintype "passive"))
      (node (ref "DLOAD") (pin "6") (pinfunction "VSS_6") (pintype "passive"))
      (node (ref "DLOAD") (pin "7") (pinfunction "VSS_7") (pintype "passive"))
      (node (ref "FAN") (pin "1") (pinfunction "1_1") (pintype "passive"))
      (node (ref "L2") (pin "1") (pinfunction "1_1") (pintype "passive"))
      (node (ref "Power") (pin "1") (pinfunction "1_1") (pintype "passive"))
      (node (ref "Q1") (pin "3") (pinfunction "S_3") (pintype "passive"))
      (node (ref "R15") (pin "2") (pinfunction "2_2") (pintype "passive"))
      (node (ref "R18") (pin "1") (pinfunction "1_1") (pintype "passive"))
      (node (ref "R19") (pin "1") (pinfunction "1_1") (pintype "passive"))
      (node (ref "R2") (pin "1") (pinfunction "1_1") (pintype "passive"))
      (node (ref "R21") (pin "1") (pinfunction "1_1") (pintype "passive"))
      (node (ref "R25") (pin "1") (pinfunction "1_1") (pintype "passive"))
      (node (ref "R30") (pin "1") (pinfunction "1_1") (pintype "passive"))
      (node (ref "U1") (pin "12") (pinfunction "VSSA_12") (pintype "power_in"))
      (node (ref "U1") (pin "18") (pinfunction "VSS_4_18") (pintype "power_in"))
      (node (ref "U1") (pin "31") (pinfunction "VSS_1_31") (pintype "power_in"))
      (node (ref "U1") (pin "47") (pinfunction "VSS_2_47") (pintype "power_in"))
      (node (ref "U1") (pin "63") (pinfunction "VSS_3_63") (pintype "power_in"))
      (node (ref "U10") (pin "2") (pinfunction "V-_2") (pintype "passive"))
      (node (ref "U11") (pin "1") (pinfunction "D_1") (pintype "passive"))
      (node (ref "U12") (pin "2") (pinfunction "V-_2") (pintype "passive"))
      (node (ref "U13") (pin "2") (pinfunction "GND_2") (pintype "passive"))
      (node (ref "U2") (pin "2") (pinfunction "GND_2") (pintype "passive"))
      (node (ref "U4") (pin "5") (pinfunction "GND_5") (pintype "passive"))
      (node (ref "U5") (pin "2") (pinfunction "GND_2") (pintype "passive"))
      (node (ref "U6") (pin "4") (pinfunction "HEATER_4") (pintype "passive"))
      (node (ref "U7") (pin "2") (pinfunction "V-_2") (pintype "passive"))
      (node (ref "U8") (pin "2") (pinfunction "VSS_2") (pintype "passive"))
      (node (ref "U9") (pin "5") (pinfunction "H_5") (pintype "passive"))
      (node (ref "X1") (pin "2") (pinfunction "GND_2") (pintype "passive"))
      (node (ref "X2") (pin "2") (pinfunction "G_2") (pintype "passive"))
      (node (ref "X2") (pin "3") (pintype "passive"))
      (node (ref "X2") (pin "4") (pinfunction "G_4") (pintype "passive"))
    )
    (net (code "21") (name "Net-(Ant.-A)") (class "Default")
      (node (ref "Ant.") (pin "1") (pinfunction "A_1") (pintype "passive"))
      (node (ref "C9") (pin "2") (pinfunction "2_2") (pintype "passive"))
      (node (ref "L2") (pin "2") (pinfunction "2_2") (pintype "passive"))
    )
    (net (code "22") (name "Net-(BUZ1-B)") (class "Default")
      (node (ref "BUZ1") (pin "2") (pinfunction "B_2") (pintype "passive"))
      (node (ref "Q1") (pin "1") (pinfunction "D_1") (pintype "passive"))
    )
    (net (code "23") (name "Net-(C15-Pad2)") (class "Default")
      (node (ref "C15") (pin "2") (pinfunction "2_2") (pintype "passive"))
      (node (ref "R3") (pin "1") (pinfunction "1_1") (pintype "passive"))
    )
    (net (code "24") (name "Net-(C16-Pad2)") (class "Default")
      (node (ref "C16") (pin "2") (pinfunction "2_2") (pintype "passive"))
      (node (ref "C9") (pin "1") (pinfunction "1_1") (pintype "passive"))
      (node (ref "R3") (pin "2") (pinfunction "2_2") (pintype "passive"))
    )
    (net (code "25") (name "Net-(C18-Pad2)") (class "Default")
      (node (ref "C18") (pin "2") (pinfunction "2_2") (pintype "passive"))
      (node (ref "R18") (pin "2") (pinfunction "2_2") (pintype "passive"))
    )
    (net (code "26") (name "Net-(D1-A)") (class "Default")
      (node (ref "D1") (pin "1") (pinfunction "A_1") (pintype "passive"))
      (node (ref "R40") (pin "1") (pinfunction "1_1") (pintype "passive"))
    )
    (net (code "27") (name "Net-(D2-K)") (class "Default")
      (node (ref "C19") (pin "2") (pinfunction "2_2") (pintype "passive"))
      (node (ref "D2") (pin "2") (pinfunction "K_2") (pintype "passive"))
      (node (ref "L3") (pin "2") (pinfunction "2_2") (pintype "passive"))
      (node (ref "U4") (pin "1") (pinfunction "SW_1") (pintype "passive"))
    )
    (net (code "28") (name "Net-(D4-A)") (class "Default")
      (node (ref "D4") (pin "1") (pinfunction "A_1") (pintype "passive"))
      (node (ref "L4") (pin "2") (pinfunction "2_2") (pintype "passive"))
      (node (ref "Power") (pin "2") (pinfunction "2_2") (pintype "passive"))
    )
    (net (code "29") (name "Net-(D7-A)") (class "Default")
      (node (ref "D7") (pin "1") (pinfunction "A_1") (pintype "passive"))
      (node (ref "R9") (pin "1") (pinfunction "1_1") (pintype "passive"))
    )
    (net (code "30") (name "Net-(FAN-Pad2)") (class "Default")
      (node (ref "FAN") (pin "2") (pinfunction "2_2") (pintype "passive"))
      (node (ref "L4") (pin "1") (pinfunction "1_1") (pintype "passive"))
    )
    (net (code "31") (name "Net-(R25-Pad2)") (class "Default")
      (node (ref "R25") (pin "2") (pinfunction "2_2") (pintype "passive"))
      (node (ref "R26") (pin "3") (pintype "passive"))
    )
    (net (code "32") (name "Net-(R26-Pad1)") (class "Default")
      (node (ref "R26") (pin "1") (pintype "passive"))
      (node (ref "R27") (pin "1") (pinfunction "1_1") (pintype "passive"))
    )
    (net (code "33") (name "Net-(R28-Pad1)") (class "Default")
      (node (ref "R28") (pin "1") (pinfunction "1_1") (pintype "passive"))
      (node (ref "U11") (pin "3") (pinfunction "C_3") (pintype "passive"))
      (node (ref "U11") (pin "4") (pinfunction "D_4") (pintype "passive"))
    )
    (net (code "34") (name "Net-(U1-BOOT0)") (class "Default")
      (node (ref "R2") (pin "2") (pinfunction "2_2") (pintype "passive"))
      (node (ref "U1") (pin "60") (pinfunction "BOOT0_60") (pintype "input"))
    )
    (net (code "35") (name "Net-(U1-OSC_IN{slash}PD0)") (class "Default")
      (node (ref "U1") (pin "5") (pinfunction "OSC_IN/PD0_5") (pintype "input"))
      (node (ref "X1") (pin "1") (pinfunction "OSC1_1") (pintype "passive"))
    )
    (net (code "36") (name "Net-(U1-OSC_OUT{slash}PD1)") (class "Default")
      (node (ref "R1") (pin "2") (pinfunction "2_2") (pintype "passive"))
      (node (ref "U1") (pin "6") (pinfunction "OSC_OUT/PD1_6") (pintype "output"))
    )
    (net (code "37") (name "Net-(U1-PA1)") (class "Default")
      (node (ref "C11") (pin "1") (pinfunction "1_1") (pintype "passive"))
      (node (ref "R10") (pin "2") (pinfunction "2_2") (pintype "passive"))
      (node (ref "U1") (pin "15") (pinfunction "PA1_15") (pintype "bidirectional"))
    )
    (net (code "38") (name "Net-(U1-PA2)") (class "Default")
      (node (ref "C12") (pin "2") (pinfunction "2_2") (pintype "passive"))
      (node (ref "R11") (pin "2") (pinfunction "2_2") (pintype "passive"))
      (node (ref "U1") (pin "16") (pinfunction "PA2_16") (pintype "bidirectional"))
    )
    (net (code "39") (name "Net-(U1-PA3)") (class "Default")
      (node (ref "C13") (pin "2") (pinfunction "2_2") (pintype "passive"))
      (node (ref "R12") (pin "2") (pinfunction "2_2") (pintype "passive"))
      (node (ref "U1") (pin "17") (pinfunction "PA3_17") (pintype "bidirectional"))
    )
    (net (code "40") (name "Net-(U1-VDDA)") (class "Default")
      (node (ref "C6") (pin "2") (pinfunction "2_2") (pintype "passive"))
      (node (ref "C7") (pin "2") (pinfunction "2_2") (pintype "passive"))
      (node (ref "L6") (pin "2") (pinfunction "2_2") (pintype "passive"))
      (node (ref "U1") (pin "13") (pinfunction "VDDA_13") (pintype "power_in"))
    )
    (net (code "41") (name "Net-(U2-BP)") (class "Default")
      (node (ref "C21") (pin "2") (pinfunction "2_2") (pintype "passive"))
      (node (ref "U2") (pin "4") (pinfunction "BP_4") (pintype "passive"))
    )
    (net (code "42") (name "Net-(U4-BST)") (class "Default")
      (node (ref "C19") (pin "1") (pinfunction "1_1") (pintype "passive"))
      (node (ref "U4") (pin "8") (pinfunction "BST_8") (pintype "passive"))
    )
    (net (code "43") (name "Net-(U4-COMP)") (class "Default")
      (node (ref "C18") (pin "1") (pinfunction "1_1") (pintype "passive"))
      (node (ref "U4") (pin "3") (pinfunction "COMP_3") (pintype "passive"))
    )
    (net (code "44") (name "Net-(U4-FB)") (class "Default")
      (node (ref "R20") (pin "1") (pinfunction "1_1") (pintype "passive"))
      (node (ref "R21") (pin "2") (pinfunction "2_2") (pintype "passive"))
      (node (ref "U4") (pin "4") (pinfunction "FB_4") (pintype "passive"))
    )
    (net (code "45") (name "Net-(U4-FREQ)") (class "Default")
      (node (ref "R19") (pin "2") (pinfunction "2_2") (pintype "passive"))
      (node (ref "U4") (pin "6") (pinfunction "FREQ_6") (pintype "passive"))
    )
    (net (code "46") (name "Net-(U5-RFO)") (class "Default")
      (node (ref "C15") (pin "1") (pinfunction "1_1") (pintype "passive"))
      (node (ref "L1") (pin "1") (pinfunction "1_1") (pintype "passive"))
      (node (ref "U5") (pin "5") (pinfunction "RFO_5") (pintype "passive"))
    )
    (net (code "47") (name "Net-(U5-XTAL)") (class "Default")
      (node (ref "U5") (pin "1") (pinfunction "XTAL_1") (pintype "passive"))
      (node (ref "X2") (pin "1") (pintype "passive"))
    )
    (net (code "48") (name "Net-(U10-+IN)") (class "Default")
      (node (ref "R15") (pin "1") (pinfunction "1_1") (pintype "passive"))
      (node (ref "U10") (pin "1") (pinfunction "+IN_1") (pintype "passive"))
      (node (ref "U9") (pin "4") (pinfunction "B_4") (pintype "passive"))
      (node (ref "U9") (pin "6") (pinfunction "B_6") (pintype "passive"))
    )
    (net (code "49") (name "Net-(U12-+IN)") (class "Default")
      (node (ref "R26") (pin "2") (pintype "passive"))
      (node (ref "U12") (pin "1") (pinfunction "+IN_1") (pintype "passive"))
    )
    (net (code "50") (name "Net-(U12--IN)") (class "Default")
      (node (ref "C27") (pin "2") (pinfunction "2_2") (pintype "passive"))
      (node (ref "R28") (pin "2") (pinfunction "2_2") (pintype "passive"))
      (node (ref "R29") (pin "1") (pinfunction "1_1") (pintype "passive"))
      (node (ref "U12") (pin "3") (pinfunction "-IN_3") (pintype "passive"))
    )
    (net (code "51") (name "Net-(U13-BP)") (class "Default")
      (node (ref "C41") (pin "2") (pinfunction "2_2") (pintype "passive"))
      (node (ref "U13") (pin "4") (pinfunction "BP_4") (pintype "passive"))
    )
    (net (code "52") (name "Net-(X1-OSC2)") (class "Default")
      (node (ref "R1") (pin "1") (pinfunction "1_1") (pintype "passive"))
      (node (ref "X1") (pin "3") (pinfunction "OSC2_3") (pintype "passive"))
    )
    (net (code "53") (name "unconnected-(DLOAD-D--Pad2)") (class "Default")
      (node (ref "DLOAD") (pin "2") (pinfunction "D-_2") (pintype "passive"))
    )
    (net (code "54") (name "unconnected-(U1-NRST-Pad7)") (class "Default")
      (node (ref "U1") (pin "7") (pinfunction "NRST_7") (pintype "bidirectional"))
    )
    (net (code "55") (name "unconnected-(U1-PA0-WKUP-Pad14)") (class "Default")
      (node (ref "U1") (pin "14") (pinfunction "PA0-WKUP_14") (pintype "bidirectional"))
    )
    (net (code "56") (name "unconnected-(U1-PA4-Pad20)") (class "Default")
      (node (ref "U1") (pin "20") (pinfunction "PA4_20") (pintype "bidirectional"))
    )
    (net (code "57") (name "unconnected-(U1-PA5-Pad21)") (class "Default")
      (node (ref "U1") (pin "21") (pinfunction "PA5_21") (pintype "bidirectional"))
    )
    (net (code "58") (name "unconnected-(U1-PA6-Pad22)") (class "Default")
      (node (ref "U1") (pin "22") (pinfunction "PA6_22") (pintype "bidirectional"))
    )
    (net (code "59") (name "unconnected-(U1-PA7-Pad23)") (class "Default")
      (node (ref "U1") (pin "23") (pinfunction "PA7_23") (pintype "bidirectional"))
    )
    (net (code "60") (name "unconnected-(U1-PA8-Pad41)") (class "Default")
      (node (ref "U1") (pin "41") (pinfunction "PA8_41") (pintype "bidirectional"))
    )
    (net (code "61") (name "unconnected-(U1-PA9-Pad42)") (class "Default")
      (node (ref "U1") (pin "42") (pinfunction "PA9_42") (pintype "bidirectional"))
    )
    (net (code "62") (name "unconnected-(U1-PA10-Pad43)") (class "Default")
      (node (ref "U1") (pin "43") (pinfunction "PA10_43") (pintype "bidirectional"))
    )
    (net (code "63") (name "unconnected-(U1-PA11-Pad44)") (class "Default")
      (node (ref "U1") (pin "44") (pinfunction "PA11_44") (pintype "bidirectional"))
    )
    (net (code "64") (name "unconnected-(U1-PA12-Pad45)") (class "Default")
      (node (ref "U1") (pin "45") (pinfunction "PA12_45") (pintype "bidirectional"))
    )
    (net (code "65") (name "unconnected-(U1-PA15{slash}JTDI-Pad50)") (class "Default")
      (node (ref "U1") (pin "50") (pinfunction "PA15/JTDI_50") (pintype "bidirectional"))
    )
    (net (code "66") (name "unconnected-(U1-PB2{slash}BOOT1-Pad28)") (class "Default")
      (node (ref "U1") (pin "28") (pinfunction "PB2/BOOT1_28") (pintype "bidirectional"))
    )
    (net (code "67") (name "unconnected-(U1-PB3{slash}JTDO-Pad55)") (class "Default")
      (node (ref "U1") (pin "55") (pinfunction "PB3/JTDO_55") (pintype "bidirectional"))
    )
    (net (code "68") (name "unconnected-(U1-PB4{slash}JNTRST-Pad56)") (class "Default")
      (node (ref "U1") (pin "56") (pinfunction "PB4/JNTRST_56") (pintype "bidirectional"))
    )
    (net (code "69") (name "unconnected-(U1-PB5-Pad57)") (class "Default")
      (node (ref "U1") (pin "57") (pinfunction "PB5_57") (pintype "bidirectional"))
    )
    (net (code "70") (name "unconnected-(U1-PB7-Pad59)") (class "Default")
      (node (ref "U1") (pin "59") (pinfunction "PB7_59") (pintype "bidirectional"))
    )
    (net (code "71") (name "unconnected-(U1-PB8-Pad61)") (class "Default")
      (node (ref "U1") (pin "61") (pinfunction "PB8_61") (pintype "bidirectional"))
    )
    (net (code "72") (name "unconnected-(U1-PB9-Pad62)") (class "Default")
      (node (ref "U1") (pin "62") (pinfunction "PB9_62") (pintype "bidirectional"))
    )
    (net (code "73") (name "unconnected-(U1-PB14-Pad35)") (class "Default")
      (node (ref "U1") (pin "35") (pinfunction "PB14_35") (pintype "bidirectional"))
    )
    (net (code "74") (name "unconnected-(U1-PB15-Pad36)") (class "Default")
      (node (ref "U1") (pin "36") (pinfunction "PB15_36") (pintype "bidirectional"))
    )
    (net (code "75") (name "unconnected-(U1-PC0-Pad8)") (class "Default")
      (node (ref "U1") (pin "8") (pinfunction "PC0_8") (pintype "bidirectional"))
    )
    (net (code "76") (name "unconnected-(U1-PC1-Pad9)") (class "Default")
      (node (ref "U1") (pin "9") (pinfunction "PC1_9") (pintype "bidirectional"))
    )
    (net (code "77") (name "unconnected-(U1-PC2-Pad10)") (class "Default")
      (node (ref "U1") (pin "10") (pinfunction "PC2_10") (pintype "bidirectional"))
    )
    (net (code "78") (name "unconnected-(U1-PC3-Pad11)") (class "Default")
      (node (ref "U1") (pin "11") (pinfunction "PC3_11") (pintype "bidirectional"))
    )
    (net (code "79") (name "unconnected-(U1-PC4-Pad24)") (class "Default")
      (node (ref "U1") (pin "24") (pinfunction "PC4_24") (pintype "bidirectional"))
    )
    (net (code "80") (name "unconnected-(U1-PC5-Pad25)") (class "Default")
      (node (ref "U1") (pin "25") (pinfunction "PC5_25") (pintype "bidirectional"))
    )
    (net (code "81") (name "unconnected-(U1-PC6-Pad37)") (class "Default")
      (node (ref "U1") (pin "37") (pinfunction "PC6_37") (pintype "bidirectional"))
    )
    (net (code "82") (name "unconnected-(U1-PC7-Pad38)") (class "Default")
      (node (ref "U1") (pin "38") (pinfunction "PC7_38") (pintype "bidirectional"))
    )
    (net (code "83") (name "unconnected-(U1-PC8-Pad39)") (class "Default")
      (node (ref "U1") (pin "39") (pinfunction "PC8_39") (pintype "bidirectional"))
    )
    (net (code "84") (name "unconnected-(U1-PC9-Pad40)") (class "Default")
      (node (ref "U1") (pin "40") (pinfunction "PC9_40") (pintype "bidirectional"))
    )
    (net (code "85") (name "unconnected-(U1-PC10-Pad51)") (class "Default")
      (node (ref "U1") (pin "51") (pinfunction "PC10_51") (pintype "bidirectional"))
    )
    (net (code "86") (name "unconnected-(U1-PC11-Pad52)") (class "Default")
      (node (ref "U1") (pin "52") (pinfunction "PC11_52") (pintype "bidirectional"))
    )
    (net (code "87") (name "unconnected-(U1-PC12-Pad53)") (class "Default")
      (node (ref "U1") (pin "53") (pinfunction "PC12_53") (pintype "bidirectional"))
    )
    (net (code "88") (name "unconnected-(U1-PC15-OSC32_OUT-Pad4)") (class "Default")
      (node (ref "U1") (pin "4") (pinfunction "PC15-OSC32_OUT_4") (pintype "bidirectional"))
    )
    (net (code "89") (name "unconnected-(U1-PD2-Pad54)") (class "Default")
      (node (ref "U1") (pin "54") (pinfunction "PD2_54") (pintype "bidirectional"))
    )
    (net (code "90") (name "unconnected-(U1-VBAT-Pad1)") (class "Default")
      (node (ref "U1") (pin "1") (pinfunction "VBAT_1") (pintype "power_in"))
    )
    (net (code "91") (name "unconnected-(U4-EN-Pad2)") (class "Default")
      (node (ref "U4") (pin "2") (pinfunction "EN_2") (pintype "passive"))
    )
    (net (code "92") (name "unconnected-(U8-NC-Pad3)") (class "Default")
      (node (ref "U8") (pin "3") (pinfunction "NC_3") (pintype "passive"))
    )
    (net (code "93") (name "unconnected-(U8-NC-Pad4)") (class "Default")
      (node (ref "U8") (pin "4") (pinfunction "NC_4") (pintype "passive"))
    )
  )
)
